# I2C_Interface.net
KiCad netlist of a schematic drawn in EAGLE
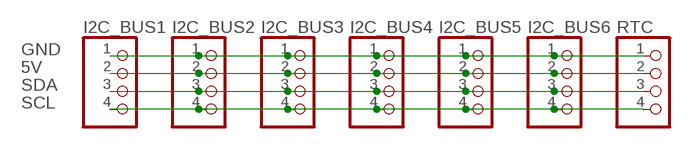
[diagram p0: schematic, sheet 1]

(export (version "E")
  (design (tool "Eeschema 10.0.6"))
  (components
    (comp (ref "I2C_BUS1")
      (value "PINHD-1X4")
      (footprint "eagle-import:1X04")
      (libsource (lib "eagle-import") (part "PINHD-1X4"))
    )
    (comp (ref "I2C_BUS2")
      (value "PINHD-1X4")
      (footprint "eagle-import:1X04")
      (libsource (lib "eagle-import") (part "PINHD-1X4"))
    )
    (comp (ref "I2C_BUS3")
      (value "PINHD-1X4")
      (footprint "eagle-import:1X04")
      (libsource (lib "eagle-import") (part "PINHD-1X4"))
    )
    (comp (ref "I2C_BUS4")
      (value "PINHD-1X4")
      (footprint "eagle-import:1X04")
      (libsource (lib "eagle-import") (part "PINHD-1X4"))
    )
    (comp (ref "I2C_BUS5")
      (value "PINHD-1X4")
      (footprint "eagle-import:1X04")
      (libsource (lib "eagle-import") (part "PINHD-1X4"))
    )
    (comp (ref "I2C_BUS6")
      (value "PINHD-1X4")
      (footprint "eagle-import:1X04")
      (libsource (lib "eagle-import") (part "PINHD-1X4"))
    )
    (comp (ref "RTC")
      (value "PINHD-1X4")
      (footprint "eagle-import:1X04")
      (libsource (lib "eagle-import") (part "PINHD-1X4"))
    )
  )
  (nets
    (net (code "1") (name "/5V") (class "Default")
      (node (ref "I2C_BUS1") (pin "2") (pinfunction "2_2") (pintype "passive"))
      (node (ref "I2C_BUS2") (pin "2") (pinfunction "2_2") (pintype "passive"))
      (node (ref "I2C_BUS3") (pin "2") (pinfunction "2_2") (pintype "passive"))
      (node (ref "I2C_BUS4") (pin "2") (pinfunction "2_2") (pintype "passive"))
      (node (ref "I2C_BUS5") (pin "2") (pinfunction "2_2") (pintype "passive"))
      (node (ref "I2C_BUS6") (pin "2") (pinfunction "2_2") (pintype "passive"))
      (node (ref "RTC") (pin "2") (pinfunction "2_2") (pintype "passive"))
    )
    (net (code "2") (name "/GND") (class "Default")
      (node (ref "I2C_BUS1") (pin "1") (pinfunction "1_1") (pintype "passive"))
      (node (ref "I2C_BUS2") (pin "1") (pinfunction "1_1") (pintype "passive"))
      (node (ref "I2C_BUS3") (pin "1") (pinfunction "1_1") (pintype "passive"))
      (node (ref "I2C_BUS4") (pin "1") (pinfunction "1_1") (pintype "passive"))
      (node (ref "I2C_BUS5") (pin "1") (pinfunction "1_1") (pintype "passive"))
      (node (ref "I2C_BUS6") (pin "1") (pinfunction "1_1") (pintype "passive"))
      (node (ref "RTC") (pin "1") (pinfunction "1_1") (pintype "passive"))
    )
    (net (code "3") (name "/SCL") (class "Default")
      (node (ref "I2C_BUS1") (pin "4") (pinfunction "4_4") (pintype "passive"))
      (node (ref "I2C_BUS2") (pin "4") (pinfunction "4_4") (pintype "passive"))
      (node (ref "I2C_BUS3") (pin "4") (pinfunction "4_4") (pintype "passive"))
      (node (ref "I2C_BUS4") (pin "4") (pinfunction "4_4") (pintype "passive"))
      (node (ref "I2C_BUS5") (pin "4") (pinfunction "4_4") (pintype "passive"))
      (node (ref "I2C_BUS6") (pin "4") (pinfunction "4_4") (pintype "passive"))
      (node (ref "RTC") (pin "4") (pinfunction "4_4") (pintype "passive"))
    )
    (net (code "4") (name "/SDA") (class "Default")
      (node (ref "I2C_BUS1") (pin "3") (pinfunction "3_3") (pintype "passive"))
      (node (ref "I2C_BUS2") (pin "3") (pinfunction "3_3") (pintype "passive"))
      (node (ref "I2C_BUS3") (pin "3") (pinfunction "3_3") (pintype "passive"))
      (node (ref "I2C_BUS4") (pin "3") (pinfunction "3_3") (pintype "passive"))
      (node (ref "I2C_BUS5") (pin "3") (pinfunction "3_3") (pintype "passive"))
      (node (ref "I2C_BUS6") (pin "3") (pinfunction "3_3") (pintype "passive"))
      (node (ref "RTC") (pin "3") (pinfunction "3_3") (pintype "passive"))
    )
  )
)
